# MotorController.net
KiCad netlist of a schematic drawn in EAGLE
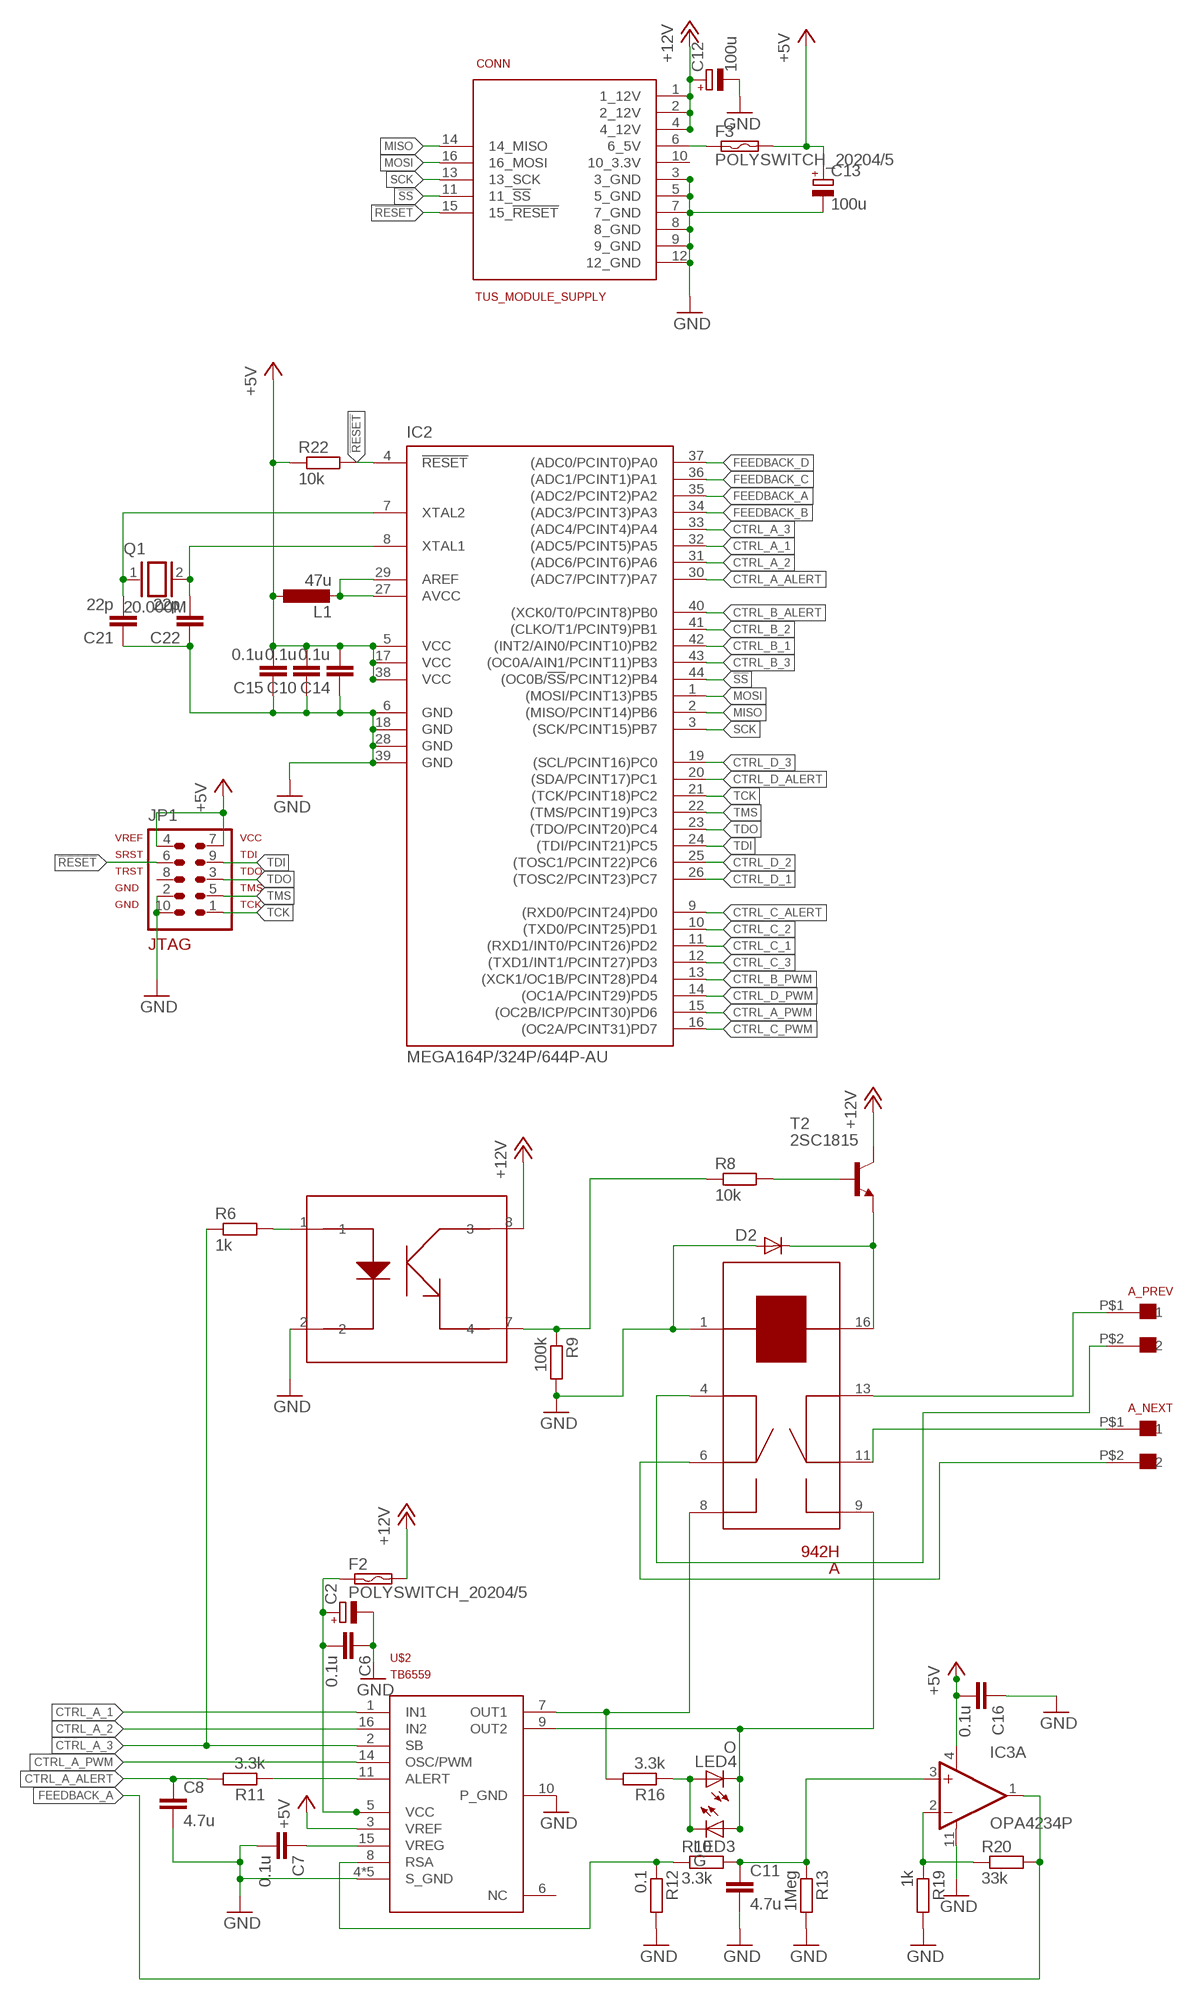
[diagram p0: schematic, sheet 1, part 1 of 2]
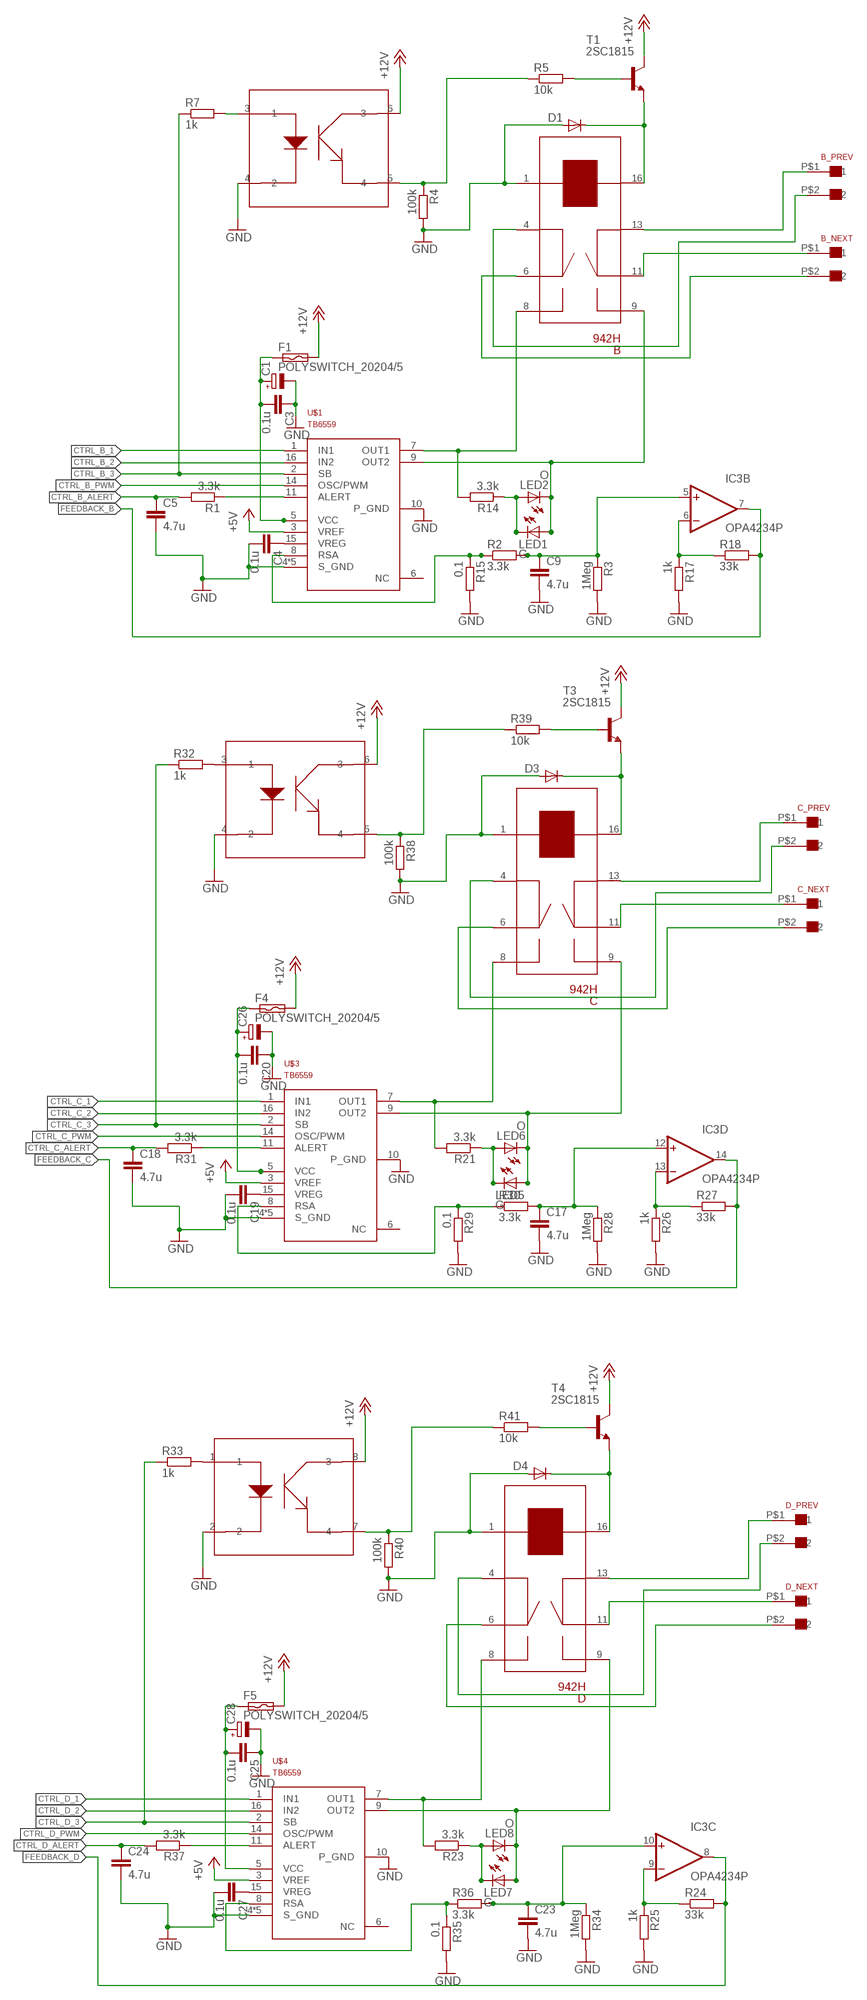
[diagram p1: schematic, sheet 1, part 2 of 2]

(export (version "E")
  (design (tool "Eeschema 10.0.6"))
  (components
    (comp (ref "A")
      (value "942H")
      (footprint "eagle-import:941H-2C-12D")
      (libsource (lib "eagle-import") (part "942H"))
    )
    (comp (ref "A_NEXT")
      (value "XH-2")
      (footprint "eagle-import:XH-2")
      (libsource (lib "eagle-import") (part "XH-2"))
    )
    (comp (ref "A_PREV")
      (value "XH-2")
      (footprint "eagle-import:XH-2")
      (libsource (lib "eagle-import") (part "XH-2"))
    )
    (comp (ref "B")
      (value "942H")
      (footprint "eagle-import:941H-2C-12D")
      (libsource (lib "eagle-import") (part "942H"))
    )
    (comp (ref "B_NEXT")
      (value "XH-2")
      (footprint "eagle-import:XH-2")
      (libsource (lib "eagle-import") (part "XH-2"))
    )
    (comp (ref "B_PREV")
      (value "XH-2")
      (footprint "eagle-import:XH-2")
      (libsource (lib "eagle-import") (part "XH-2"))
    )
    (comp (ref "C")
      (value "942H")
      (footprint "eagle-import:941H-2C-12D")
      (libsource (lib "eagle-import") (part "942H"))
    )
    (comp (ref "C1")
      (value "CPOL-EUE2,5-6E")
      (footprint "eagle-import:E2,5-6E")
      (libsource (lib "eagle-import") (part "CPOL-EUE2,5-6E"))
    )
    (comp (ref "C2")
      (value "CPOL-EUE2,5-6E")
      (footprint "eagle-import:E2,5-6E")
      (libsource (lib "eagle-import") (part "CPOL-EUE2,5-6E"))
    )
    (comp (ref "C3")
      (value "0.1u")
      (footprint "eagle-import:C0603")
      (libsource (lib "eagle-import") (part "C-EUC0603"))
    )
    (comp (ref "C4")
      (value "0.1u")
      (footprint "eagle-import:C0603")
      (libsource (lib "eagle-import") (part "C-EUC0603"))
    )
    (comp (ref "C5")
      (value "4.7u")
      (footprint "eagle-import:C0603")
      (libsource (lib "eagle-import") (part "C-EUC0603"))
    )
    (comp (ref "C6")
      (value "0.1u")
      (footprint "eagle-import:C0603")
      (libsource (lib "eagle-import") (part "C-EUC0603"))
    )
    (comp (ref "C7")
      (value "0.1u")
      (footprint "eagle-import:C0603")
      (libsource (lib "eagle-import") (part "C-EUC0603"))
    )
    (comp (ref "C8")
      (value "4.7u")
      (footprint "eagle-import:C0603")
      (libsource (lib "eagle-import") (part "C-EUC0603"))
    )
    (comp (ref "C9")
      (value "4.7u")
      (footprint "eagle-import:C0603")
      (libsource (lib "eagle-import") (part "C-EUC0603"))
    )
    (comp (ref "C10")
      (value "0.1u")
      (footprint "eagle-import:C0603")
      (libsource (lib "eagle-import") (part "C-EUC0603"))
    )
    (comp (ref "C11")
      (value "4.7u")
      (footprint "eagle-import:C0603")
      (libsource (lib "eagle-import") (part "C-EUC0603"))
    )
    (comp (ref "C12")
      (value "100u")
      (footprint "eagle-import:E2,5-6")
      (libsource (lib "eagle-import") (part "CPOL-EUE2.5-6"))
    )
    (comp (ref "C13")
      (value "100u")
      (footprint "eagle-import:E2-5")
      (libsource (lib "eagle-import") (part "CPOL-EUE2-5"))
    )
    (comp (ref "C14")
      (value "0.1u")
      (footprint "eagle-import:C0603")
      (libsource (lib "eagle-import") (part "C-EUC0603"))
    )
    (comp (ref "C15")
      (value "0.1u")
      (footprint "eagle-import:C0603")
      (libsource (lib "eagle-import") (part "C-EUC0603"))
    )
    (comp (ref "C16")
      (value "0.1u")
      (footprint "eagle-import:C0603")
      (libsource (lib "eagle-import") (part "C-EUC0603"))
    )
    (comp (ref "C17")
      (value "4.7u")
      (footprint "eagle-import:C0603")
      (libsource (lib "eagle-import") (part "C-EUC0603"))
    )
    (comp (ref "C18")
      (value "4.7u")
      (footprint "eagle-import:C0603")
      (libsource (lib "eagle-import") (part "C-EUC0603"))
    )
    (comp (ref "C19")
      (value "0.1u")
      (footprint "eagle-import:C0603")
      (libsource (lib "eagle-import") (part "C-EUC0603"))
    )
    (comp (ref "C20")
      (value "0.1u")
      (footprint "eagle-import:C0603")
      (libsource (lib "eagle-import") (part "C-EUC0603"))
    )
    (comp (ref "C21")
      (value "22p")
      (footprint "eagle-import:C0603")
      (libsource (lib "eagle-import") (part "C-EUC0603"))
    )
    (comp (ref "C22")
      (value "22p")
      (footprint "eagle-import:C0603")
      (libsource (lib "eagle-import") (part "C-EUC0603"))
    )
    (comp (ref "C23")
      (value "4.7u")
      (footprint "eagle-import:C0603")
      (libsource (lib "eagle-import") (part "C-EUC0603"))
    )
    (comp (ref "C24")
      (value "4.7u")
      (footprint "eagle-import:C0603")
      (libsource (lib "eagle-import") (part "C-EUC0603"))
    )
    (comp (ref "C25")
      (value "0.1u")
      (footprint "eagle-import:C0603")
      (libsource (lib "eagle-import") (part "C-EUC0603"))
    )
    (comp (ref "C26")
      (value "CPOL-EUE2,5-6E")
      (footprint "eagle-import:E2,5-6E")
      (libsource (lib "eagle-import") (part "CPOL-EUE2,5-6E"))
    )
    (comp (ref "C27")
      (value "0.1u")
      (footprint "eagle-import:C0603")
      (libsource (lib "eagle-import") (part "C-EUC0603"))
    )
    (comp (ref "C28")
      (value "CPOL-EUE2,5-6E")
      (footprint "eagle-import:E2,5-6E")
      (libsource (lib "eagle-import") (part "CPOL-EUE2,5-6E"))
    )
    (comp (ref "CONN")
      (value "TUS_MODULE_SUPPLY")
      (footprint "eagle-import:2X08")
      (libsource (lib "eagle-import") (part "TUS_MODULE_SUPPLY"))
    )
    (comp (ref "C_NEXT")
      (value "XH-2")
      (footprint "eagle-import:XH-2")
      (libsource (lib "eagle-import") (part "XH-2"))
    )
    (comp (ref "C_PREV")
      (value "XH-2")
      (footprint "eagle-import:XH-2")
      (libsource (lib "eagle-import") (part "XH-2"))
    )
    (comp (ref "D")
      (value "942H")
      (footprint "eagle-import:941H-2C-12D")
      (libsource (lib "eagle-import") (part "942H"))
    )
    (comp (ref "D1")
      (value "1N4148DO35-7")
      (footprint "eagle-import:DO35-7")
      (libsource (lib "eagle-import") (part "1N4148DO35-7"))
    )
    (comp (ref "D2")
      (value "1N4148DO35-7")
      (footprint "eagle-import:DO35-7")
      (libsource (lib "eagle-import") (part "1N4148DO35-7"))
    )
    (comp (ref "D3")
      (value "1N4148DO35-7")
      (footprint "eagle-import:DO35-7")
      (libsource (lib "eagle-import") (part "1N4148DO35-7"))
    )
    (comp (ref "D4")
      (value "1N4148DO35-7")
      (footprint "eagle-import:DO35-7")
      (libsource (lib "eagle-import") (part "1N4148DO35-7"))
    )
    (comp (ref "D_NEXT")
      (value "XH-2")
      (footprint "eagle-import:XH-2")
      (libsource (lib "eagle-import") (part "XH-2"))
    )
    (comp (ref "D_PREV")
      (value "XH-2")
      (footprint "eagle-import:XH-2")
      (libsource (lib "eagle-import") (part "XH-2"))
    )
    (comp (ref "F1")
      (value "POLYSWITCH_20204/5")
      (footprint "eagle-import:0204_5")
      (libsource (lib "eagle-import") (part "POLYSWITCH_20204/5"))
    )
    (comp (ref "F2")
      (value "POLYSWITCH_20204/5")
      (footprint "eagle-import:0204_5")
      (libsource (lib "eagle-import") (part "POLYSWITCH_20204/5"))
    )
    (comp (ref "F3")
      (value "POLYSWITCH_20204/5")
      (footprint "eagle-import:0204_5")
      (libsource (lib "eagle-import") (part "POLYSWITCH_20204/5"))
    )
    (comp (ref "F4")
      (value "POLYSWITCH_20204/5")
      (footprint "eagle-import:0204_5")
      (libsource (lib "eagle-import") (part "POLYSWITCH_20204/5"))
    )
    (comp (ref "F5")
      (value "POLYSWITCH_20204/5")
      (footprint "eagle-import:0204_5")
      (libsource (lib "eagle-import") (part "POLYSWITCH_20204/5"))
    )
    (comp (ref "IC1")
      (value "TLP621-2")
      (footprint "eagle-import:SOCKET-08")
      (libsource (lib "eagle-import") (part "TLP621-2"))
    )
    (comp (ref "IC2")
      (value "MEGA164P/324P/644P-AU")
      (footprint "eagle-import:TQFP44")
      (libsource (lib "eagle-import") (part "MEGA164P/324P/644P-AU"))
    )
    (comp (ref "IC3")
      (value "OPA4234P")
      (footprint "eagle-import:DIL14")
      (libsource (lib "eagle-import") (part "OPA4234P"))
    )
    (comp (ref "IC4")
      (value "TLP621-2")
      (footprint "eagle-import:SOCKET-08")
      (libsource (lib "eagle-import") (part "TLP621-2"))
    )
    (comp (ref "JP1")
      (value "AVR-JTAG-10")
      (footprint "eagle-import:AVR-JTAG-10")
      (libsource (lib "eagle-import") (part "AVR-JTAG-10"))
    )
    (comp (ref "L1")
      (value "47u")
      (footprint "eagle-import:L3216C")
      (libsource (lib "eagle-import") (part "L-EUL3216C"))
    )
    (comp (ref "LED1")
      (value "G")
      (footprint "eagle-import:LED3MM")
      (libsource (lib "eagle-import") (part "LED3MM"))
    )
    (comp (ref "LED2")
      (value "O")
      (footprint "eagle-import:LED3MM")
      (libsource (lib "eagle-import") (part "LED3MM"))
    )
    (comp (ref "LED3")
      (value "G")
      (footprint "eagle-import:LED3MM")
      (libsource (lib "eagle-import") (part "LED3MM"))
    )
    (comp (ref "LED4")
      (value "O")
      (footprint "eagle-import:LED3MM")
      (libsource (lib "eagle-import") (part "LED3MM"))
    )
    (comp (ref "LED5")
      (value "G")
      (footprint "eagle-import:LED3MM")
      (libsource (lib "eagle-import") (part "LED3MM"))
    )
    (comp (ref "LED6")
      (value "O")
      (footprint "eagle-import:LED3MM")
      (libsource (lib "eagle-import") (part "LED3MM"))
    )
    (comp (ref "LED7")
      (value "G")
      (footprint "eagle-import:LED3MM")
      (libsource (lib "eagle-import") (part "LED3MM"))
    )
    (comp (ref "LED8")
      (value "O")
      (footprint "eagle-import:LED3MM")
      (libsource (lib "eagle-import") (part "LED3MM"))
    )
    (comp (ref "Q1")
      (value "20.000M")
      (footprint "eagle-import:QS")
      (libsource (lib "eagle-import") (part "XTAL/S"))
    )
    (comp (ref "R1")
      (value "3.3k")
      (footprint "eagle-import:R0603")
      (libsource (lib "eagle-import") (part "R-EU_R0603"))
    )
    (comp (ref "R2")
      (value "3.3k")
      (footprint "eagle-import:R0603")
      (libsource (lib "eagle-import") (part "R-EU_R0603"))
    )
    (comp (ref "R3")
      (value "1Meg")
      (footprint "eagle-import:R0603")
      (libsource (lib "eagle-import") (part "R-EU_R0603"))
    )
    (comp (ref "R4")
      (value "100k")
      (footprint "eagle-import:R0603")
      (libsource (lib "eagle-import") (part "R-EU_R0603"))
    )
    (comp (ref "R5")
      (value "10k")
      (footprint "eagle-import:R0603")
      (libsource (lib "eagle-import") (part "R-EU_R0603"))
    )
    (comp (ref "R6")
      (value "1k")
      (footprint "eagle-import:R0603")
      (libsource (lib "eagle-import") (part "R-EU_R0603"))
    )
    (comp (ref "R7")
      (value "1k")
      (footprint "eagle-import:R0603")
      (libsource (lib "eagle-import") (part "R-EU_R0603"))
    )
    (comp (ref "R8")
      (value "10k")
      (footprint "eagle-import:R0603")
      (libsource (lib "eagle-import") (part "R-EU_R0603"))
    )
    (comp (ref "R9")
      (value "100k")
      (footprint "eagle-import:R0603")
      (libsource (lib "eagle-import") (part "R-EU_R0603"))
    )
    (comp (ref "R10")
      (value "3.3k")
      (footprint "eagle-import:R0603")
      (libsource (lib "eagle-import") (part "R-EU_R0603"))
    )
    (comp (ref "R11")
      (value "3.3k")
      (footprint "eagle-import:R0603")
      (libsource (lib "eagle-import") (part "R-EU_R0603"))
    )
    (comp (ref "R12")
      (value "0.1")
      (footprint "eagle-import:R1206")
      (libsource (lib "eagle-import") (part "R-EU_R1206"))
    )
    (comp (ref "R13")
      (value "1Meg")
      (footprint "eagle-import:R0603")
      (libsource (lib "eagle-import") (part "R-EU_R0603"))
    )
    (comp (ref "R14")
      (value "3.3k")
      (footprint "eagle-import:R0603")
      (libsource (lib "eagle-import") (part "R-EU_R0603"))
    )
    (comp (ref "R15")
      (value "0.1")
      (footprint "eagle-import:R1206")
      (libsource (lib "eagle-import") (part "R-EU_R1206"))
    )
    (comp (ref "R16")
      (value "3.3k")
      (footprint "eagle-import:R0603")
      (libsource (lib "eagle-import") (part "R-EU_R0603"))
    )
    (comp (ref "R17")
      (value "1k")
      (footprint "eagle-import:R0603")
      (libsource (lib "eagle-import") (part "R-EU_R0603"))
    )
    (comp (ref "R18")
      (value "33k")
      (footprint "eagle-import:R0603")
      (libsource (lib "eagle-import") (part "R-EU_R0603"))
    )
    (comp (ref "R19")
      (value "1k")
      (footprint "eagle-import:R0603")
      (libsource (lib "eagle-import") (part "R-EU_R0603"))
    )
    (comp (ref "R20")
      (value "33k")
      (footprint "eagle-import:R0603")
      (libsource (lib "eagle-import") (part "R-EU_R0603"))
    )
    (comp (ref "R21")
      (value "3.3k")
      (footprint "eagle-import:R0603")
      (libsource (lib "eagle-import") (part "R-EU_R0603"))
    )
    (comp (ref "R22")
      (value "10k")
      (footprint "eagle-import:R0603")
      (libsource (lib "eagle-import") (part "R-EU_R0603"))
    )
    (comp (ref "R23")
      (value "3.3k")
      (footprint "eagle-import:R0603")
      (libsource (lib "eagle-import") (part "R-EU_R0603"))
    )
    (comp (ref "R24")
      (value "33k")
      (footprint "eagle-import:R0603")
      (libsource (lib "eagle-import") (part "R-EU_R0603"))
    )
    (comp (ref "R25")
      (value "1k")
      (footprint "eagle-import:R0603")
      (libsource (lib "eagle-import") (part "R-EU_R0603"))
    )
    (comp (ref "R26")
      (value "1k")
      (footprint "eagle-import:R0603")
      (libsource (lib "eagle-import") (part "R-EU_R0603"))
    )
    (comp (ref "R27")
      (value "33k")
      (footprint "eagle-import:R0603")
      (libsource (lib "eagle-import") (part "R-EU_R0603"))
    )
    (comp (ref "R28")
      (value "1Meg")
      (footprint "eagle-import:R0603")
      (libsource (lib "eagle-import") (part "R-EU_R0603"))
    )
    (comp (ref "R29")
      (value "0.1")
      (footprint "eagle-import:R1206")
      (libsource (lib "eagle-import") (part "R-EU_R1206"))
    )
    (comp (ref "R30")
      (value "3.3k")
      (footprint "eagle-import:R0603")
      (libsource (lib "eagle-import") (part "R-EU_R0603"))
    )
    (comp (ref "R31")
      (value "3.3k")
      (footprint "eagle-import:R0603")
      (libsource (lib "eagle-import") (part "R-EU_R0603"))
    )
    (comp (ref "R32")
      (value "1k")
      (footprint "eagle-import:R0603")
      (libsource (lib "eagle-import") (part "R-EU_R0603"))
    )
    (comp (ref "R33")
      (value "1k")
      (footprint "eagle-import:R0603")
      (libsource (lib "eagle-import") (part "R-EU_R0603"))
    )
    (comp (ref "R34")
      (value "1Meg")
      (footprint "eagle-import:R0603")
      (libsource (lib "eagle-import") (part "R-EU_R0603"))
    )
    (comp (ref "R35")
      (value "0.1")
      (footprint "eagle-import:R1206")
      (libsource (lib "eagle-import") (part "R-EU_R1206"))
    )
    (comp (ref "R36")
      (value "3.3k")
      (footprint "eagle-import:R0603")
      (libsource (lib "eagle-import") (part "R-EU_R0603"))
    )
    (comp (ref "R37")
      (value "3.3k")
      (footprint "eagle-import:R0603")
      (libsource (lib "eagle-import") (part "R-EU_R0603"))
    )
    (comp (ref "R38")
      (value "100k")
      (footprint "eagle-import:R0603")
      (libsource (lib "eagle-import") (part "R-EU_R0603"))
    )
    (comp (ref "R39")
      (value "10k")
      (footprint "eagle-import:R0603")
      (libsource (lib "eagle-import") (part "R-EU_R0603"))
    )
    (comp (ref "R40")
      (value "100k")
      (footprint "eagle-import:R0603")
      (libsource (lib "eagle-import") (part "R-EU_R0603"))
    )
    (comp (ref "R41")
      (value "10k")
      (footprint "eagle-import:R0603")
      (libsource (lib "eagle-import") (part "R-EU_R0603"))
    )
    (comp (ref "T1")
      (value "2SC1815")
      (footprint "eagle-import:TO92-ECB")
      (libsource (lib "eagle-import") (part "2SC1815"))
    )
    (comp (ref "T2")
      (value "2SC1815")
      (footprint "eagle-import:TO92-ECB")
      (libsource (lib "eagle-import") (part "2SC1815"))
    )
    (comp (ref "T3")
      (value "2SC1815")
      (footprint "eagle-import:TO92-ECB")
      (libsource (lib "eagle-import") (part "2SC1815"))
    )
    (comp (ref "T4")
      (value "2SC1815")
      (footprint "eagle-import:TO92-ECB")
      (libsource (lib "eagle-import") (part "2SC1815"))
    )
    (comp (ref "U$1")
      (value "TB6559")
      (footprint "eagle-import:HSOP-16")
      (libsource (lib "eagle-import") (part "TB6559"))
    )
    (comp (ref "U$2")
      (value "TB6559")
      (footprint "eagle-import:HSOP-16")
      (libsource (lib "eagle-import") (part "TB6559"))
    )
    (comp (ref "U$3")
      (value "TB6559")
      (footprint "eagle-import:HSOP-16")
      (libsource (lib "eagle-import") (part "TB6559"))
    )
    (comp (ref "U$4")
      (value "TB6559")
      (footprint "eagle-import:HSOP-16")
      (libsource (lib "eagle-import") (part "TB6559"))
    )
  )
  (nets
    (net (code "1") (name "+5V") (class "Default")
      (node (ref "C10") (pin "2") (pinfunction "2_2") (pintype "passive"))
      (node (ref "C13") (pin "+") (pinfunction "+_+") (pintype "passive"))
      (node (ref "C14") (pin "2") (pinfunction "2_2") (pintype "passive"))
      (node (ref "C15") (pin "2") (pinfunction "2_2") (pintype "passive"))
      (node (ref "C16") (pin "2") (pinfunction "2_2") (pintype "passive"))
      (node (ref "F3") (pin "2") (pinfunction "2_2") (pintype "passive"))
      (node (ref "IC2") (pin "17") (pinfunction "VCC_17") (pintype "power_in"))
      (node (ref "IC2") (pin "38") (pinfunction "VCC_38") (pintype "power_in"))
      (node (ref "IC2") (pin "5") (pinfunction "VCC_5") (pintype "power_in"))
      (node (ref "IC3") (pin "4") (pinfunction "V+_4") (pintype "power_in"))
      (node (ref "JP1") (pin "4") (pinfunction "4_4") (pintype "passive"))
      (node (ref "JP1") (pin "7") (pinfunction "7_7") (pintype "passive"))
      (node (ref "L1") (pin "1") (pinfunction "1_1") (pintype "passive"))
      (node (ref "R22") (pin "1") (pinfunction "1_1") (pintype "passive"))
      (node (ref "U$1") (pin "3") (pinfunction "VREF_3") (pintype "bidirectional"))
      (node (ref "U$2") (pin "3") (pinfunction "VREF_3") (pintype "bidirectional"))
      (node (ref "U$3") (pin "3") (pinfunction "VREF_3") (pintype "bidirectional"))
      (node (ref "U$4") (pin "3") (pinfunction "VREF_3") (pintype "bidirectional"))
    )
    (net (code "2") (name "+12V") (class "Default")
      (node (ref "C12") (pin "+") (pinfunction "+_+") (pintype "passive"))
      (node (ref "CONN") (pin "1") (pinfunction "1_12V_1") (pintype "bidirectional"))
      (node (ref "CONN") (pin "2") (pinfunction "2_12V_2") (pintype "bidirectional"))
      (node (ref "CONN") (pin "4") (pinfunction "4_12V_4") (pintype "bidirectional"))
      (node (ref "F1") (pin "2") (pinfunction "2_2") (pintype "passive"))
      (node (ref "F2") (pin "2") (pinfunction "2_2") (pintype "passive"))
      (node (ref "F4") (pin "2") (pinfunction "2_2") (pintype "passive"))
      (node (ref "F5") (pin "2") (pinfunction "2_2") (pintype "passive"))
      (node (ref "IC1") (pin "6") (pinfunction "3_6") (pintype "bidirectional"))
      (node (ref "IC1") (pin "8") (pinfunction "3_8") (pintype "bidirectional"))
      (node (ref "IC4") (pin "6") (pinfunction "3_6") (pintype "bidirectional"))
      (node (ref "IC4") (pin "8") (pinfunction "3_8") (pintype "bidirectional"))
      (node (ref "T1") (pin "C") (pinfunction "C_C") (pintype "passive"))
      (node (ref "T2") (pin "C") (pinfunction "C_C") (pintype "passive"))
      (node (ref "T3") (pin "C") (pinfunction "C_C") (pintype "passive"))
      (node (ref "T4") (pin "C") (pinfunction "C_C") (pintype "passive"))
    )
    (net (code "3") (name "/~{RESET}") (class "Default")
      (node (ref "CONN") (pin "15") (pinfunction "15_~{RESET}_15") (pintype "bidirectional"))
      (node (ref "IC2") (pin "4") (pinfunction "~{RESET}_4") (pintype "input"))
      (node (ref "JP1") (pin "6") (pinfunction "6_6") (pintype "passive"))
      (node (ref "R22") (pin "2") (pinfunction "2_2") (pintype "passive"))
    )
    (net (code "4") (name "/~{SS}") (class "Default")
      (node (ref "CONN") (pin "11") (pinfunction "11_~{SS}_11") (pintype "bidirectional"))
      (node (ref "IC2") (pin "44") (pinfunction "(OC0B/~{SS}/PCINT12)PB4_44") (pintype "bidirectional"))
    )
    (net (code "5") (name "CTRL_A_1") (class "Default")
      (node (ref "IC2") (pin "32") (pinfunction "(ADC5/PCINT5)PA5_32") (pintype "bidirectional"))
      (node (ref "U$2") (pin "1") (pinfunction "IN1_1") (pintype "bidirectional"))
    )
    (net (code "6") (name "CTRL_A_2") (class "Default")
      (node (ref "IC2") (pin "31") (pinfunction "(ADC6/PCINT6)PA6_31") (pintype "bidirectional"))
      (node (ref "U$2") (pin "16") (pinfunction "IN2_16") (pintype "bidirectional"))
    )
    (net (code "7") (name "CTRL_A_3") (class "Default")
      (node (ref "IC2") (pin "33") (pinfunction "(ADC4/PCINT4)PA4_33") (pintype "bidirectional"))
      (node (ref "R6") (pin "1") (pinfunction "1_1") (pintype "passive"))
      (node (ref "U$2") (pin "2") (pinfunction "SB_2") (pintype "bidirectional"))
    )
    (net (code "8") (name "CTRL_A_ALERT") (class "Default")
      (node (ref "C8") (pin "1") (pinfunction "1_1") (pintype "passive"))
      (node (ref "IC2") (pin "30") (pinfunction "(ADC7/PCINT7)PA7_30") (pintype "bidirectional"))
      (node (ref "R11") (pin "2") (pinfunction "2_2") (pintype "passive"))
    )
    (net (code "9") (name "CTRL_A_PWM") (class "Default")
      (node (ref "IC2") (pin "15") (pinfunction "(OC2B/ICP/PCINT30)PD6_15") (pintype "bidirectional"))
      (node (ref "U$2") (pin "14") (pinfunction "OSC/PWM_14") (pintype "bidirectional"))
    )
    (net (code "10") (name "CTRL_B_1") (class "Default")
      (node (ref "IC2") (pin "42") (pinfunction "(INT2/AIN0/PCINT10)PB2_42") (pintype "bidirectional"))
      (node (ref "U$1") (pin "1") (pinfunction "IN1_1") (pintype "bidirectional"))
    )
    (net (code "11") (name "CTRL_B_2") (class "Default")
      (node (ref "IC2") (pin "41") (pinfunction "(CLKO/T1/PCINT9)PB1_41") (pintype "bidirectional"))
      (node (ref "U$1") (pin "16") (pinfunction "IN2_16") (pintype "bidirectional"))
    )
    (net (code "12") (name "CTRL_B_3") (class "Default")
      (node (ref "IC2") (pin "43") (pinfunction "(OC0A/AIN1/PCINT11)PB3_43") (pintype "bidirectional"))
      (node (ref "R7") (pin "1") (pinfunction "1_1") (pintype "passive"))
      (node (ref "U$1") (pin "2") (pinfunction "SB_2") (pintype "bidirectional"))
    )
    (net (code "13") (name "CTRL_B_ALERT") (class "Default")
      (node (ref "C5") (pin "1") (pinfunction "1_1") (pintype "passive"))
      (node (ref "IC2") (pin "40") (pinfunction "(XCK0/T0/PCINT8)PB0_40") (pintype "bidirectional"))
      (node (ref "R1") (pin "2") (pinfunction "2_2") (pintype "passive"))
    )
    (net (code "14") (name "CTRL_B_PWM") (class "Default")
      (node (ref "IC2") (pin "13") (pinfunction "(XCK1/OC1B/PCINT28)PD4_13") (pintype "bidirectional"))
      (node (ref "U$1") (pin "14") (pinfunction "OSC/PWM_14") (pintype "bidirectional"))
    )
    (net (code "15") (name "CTRL_C_1") (class "Default")
      (node (ref "IC2") (pin "11") (pinfunction "(RXD1/INT0/PCINT26)PD2_11") (pintype "bidirectional"))
      (node (ref "U$3") (pin "1") (pinfunction "IN1_1") (pintype "bidirectional"))
    )
    (net (code "16") (name "CTRL_C_2") (class "Default")
      (node (ref "IC2") (pin "10") (pinfunction "(TXD0/PCINT25)PD1_10") (pintype "bidirectional"))
      (node (ref "U$3") (pin "16") (pinfunction "IN2_16") (pintype "bidirectional"))
    )
    (net (code "17") (name "CTRL_C_3") (class "Default")
      (node (ref "IC2") (pin "12") (pinfunction "(TXD1/INT1/PCINT27)PD3_12") (pintype "bidirectional"))
      (node (ref "R32") (pin "1") (pinfunction "1_1") (pintype "passive"))
      (node (ref "U$3") (pin "2") (pinfunction "SB_2") (pintype "bidirectional"))
    )
    (net (code "18") (name "CTRL_C_ALERT") (class "Default")
      (node (ref "C18") (pin "1") (pinfunction "1_1") (pintype "passive"))
      (node (ref "IC2") (pin "9") (pinfunction "(RXD0/PCINT24)PD0_9") (pintype "bidirectional"))
      (node (ref "R31") (pin "2") (pinfunction "2_2") (pintype "passive"))
    )
    (net (code "19") (name "CTRL_C_PWM") (class "Default")
      (node (ref "IC2") (pin "16") (pinfunction "(OC2A/PCINT31)PD7_16") (pintype "bidirectional"))
      (node (ref "U$3") (pin "14") (pinfunction "OSC/PWM_14") (pintype "bidirectional"))
    )
    (net (code "20") (name "CTRL_D_1") (class "Default")
      (node (ref "IC2") (pin "26") (pinfunction "(TOSC2/PCINT23)PC7_26") (pintype "bidirectional"))
      (node (ref "U$4") (pin "1") (pinfunction "IN1_1") (pintype "bidirectional"))
    )
    (net (code "21") (name "CTRL_D_2") (class "Default")
      (node (ref "IC2") (pin "25") (pinfunction "(TOSC1/PCINT22)PC6_25") (pintype "bidirectional"))
      (node (ref "U$4") (pin "16") (pinfunction "IN2_16") (pintype "bidirectional"))
    )
    (net (code "22") (name "CTRL_D_3") (class "Default")
      (node (ref "IC2") (pin "19") (pinfunction "(SCL/PCINT16)PC0_19") (pintype "bidirectional"))
      (node (ref "R33") (pin "1") (pinfunction "1_1") (pintype "passive"))
      (node (ref "U$4") (pin "2") (pinfunction "SB_2") (pintype "bidirectional"))
    )
    (net (code "23") (name "CTRL_D_ALERT") (class "Default")
      (node (ref "C24") (pin "1") (pinfunction "1_1") (pintype "passive"))
      (node (ref "IC2") (pin "20") (pinfunction "(SDA/PCINT17)PC1_20") (pintype "bidirectional"))
      (node (ref "R37") (pin "2") (pinfunction "2_2") (pintype "passive"))
    )
    (net (code "24") (name "CTRL_D_PWM") (class "Default")
      (node (ref "IC2") (pin "14") (pinfunction "(OC1A/PCINT29)PD5_14") (pintype "bidirectional"))
      (node (ref "U$4") (pin "14") (pinfunction "OSC/PWM_14") (pintype "bidirectional"))
    )
    (net (code "25") (name "FEEDBACK_A") (class "Default")
      (node (ref "IC2") (pin "35") (pinfunction "(ADC2/PCINT2)PA2_35") (pintype "bidirectional"))
      (node (ref "IC3") (pin "1") (pinfunction "OUT_1") (pintype "output"))
      (node (ref "R20") (pin "2") (pinfunction "2_2") (pintype "passive"))
    )
    (net (code "26") (name "FEEDBACK_B") (class "Default")
      (node (ref "IC2") (pin "34") (pinfunction "(ADC3/PCINT3)PA3_34") (pintype "bidirectional"))
      (node (ref "IC3") (pin "7") (pinfunction "OUT_7") (pintype "output"))
      (node (ref "R18") (pin "2") (pinfunction "2_2") (pintype "passive"))
    )
    (net (code "27") (name "FEEDBACK_C") (class "Default")
      (node (ref "IC2") (pin "36") (pinfunction "(ADC1/PCINT1)PA1_36") (pintype "bidirectional"))
      (node (ref "IC3") (pin "14") (pinfunction "OUT_14") (pintype "output"))
      (node (ref "R27") (pin "2") (pinfunction "2_2") (pintype "passive"))
    )
    (net (code "28") (name "FEEDBACK_D") (class "Default")
      (node (ref "IC2") (pin "37") (pinfunction "(ADC0/PCINT0)PA0_37") (pintype "bidirectional"))
      (node (ref "IC3") (pin "8") (pinfunction "OUT_8") (pintype "output"))
      (node (ref "R24") (pin "2") (pinfunction "2_2") (pintype "passive"))
    )
    (net (code "29") (name "GND") (class "Default")
      (node (ref "A") (pin "1") (pinfunction "4_1") (pintype "bidirectional"))
      (node (ref "B") (pin "1") (pinfunction "4_1") (pintype "bidirectional"))
      (node (ref "C") (pin "1") (pinfunction "4_1") (pintype "bidirectional"))
      (node (ref "C1") (pin "-") (pinfunction "-_-") (pintype "passive"))
      (node (ref "C10") (pin "1") (pinfunction "1_1") (pintype "passive"))
      (node (ref "C11") (pin "2") (pinfunction "2_2") (pintype "passive"))
      (node (ref "C12") (pin "-") (pinfunction "-_-") (pintype "passive"))
      (node (ref "C13") (pin "-") (pinfunction "-_-") (pintype "passive"))
      (node (ref "C14") (pin "1") (pinfunction "1_1") (pintype "passive"))
      (node (ref "C15") (pin "1") (pinfunction "1_1") (pintype "passive"))
      (node (ref "C16") (pin "1") (pinfunction "1_1") (pintype "passive"))
      (node (ref "C17") (pin "2") (pinfunction "2_2") (pintype "passive"))
      (node (ref "C18") (pin "2") (pinfunction "2_2") (pintype "passive"))
      (node (ref "C19") (pin "2") (pinfunction "2_2") (pintype "passive"))
      (node (ref "C2") (pin "-") (pinfunction "-_-") (pintype "passive"))
      (node (ref "C20") (pin "1") (pinfunction "1_1") (pintype "passive"))
      (node (ref "C21") (pin "1") (pinfunction "1_1") (pintype "passive"))
      (node (ref "C22") (pin "1") (pinfunction "1_1") (pintype "passive"))
      (node (ref "C23") (pin "2") (pinfunction "2_2") (pintype "passive"))
      (node (ref "C24") (pin "2") (pinfunction "2_2") (pintype "passive"))
      (node (ref "C25") (pin "1") (pinfunction "1_1") (pintype "passive"))
      (node (ref "C26") (pin "-") (pinfunction "-_-") (pintype "passive"))
      (node (ref "C27") (pin "2") (pinfunction "2_2") (pintype "passive"))
      (node (ref "C28") (pin "-") (pinfunction "-_-") (pintype "passive"))
      (node (ref "C3") (pin "1") (pinfunction "1_1") (pintype "passive"))
      (node (ref "C4") (pin "2") (pinfunction "2_2") (pintype "passive"))
      (node (ref "C5") (pin "2") (pinfunction "2_2") (pintype "passive"))
      (node (ref "C6") (pin "1") (pinfunction "1_1") (pintype "passive"))
      (node (ref "C7") (pin "2") (pinfunction "2_2") (pintype "passive"))
      (node (ref "C8") (pin "2") (pinfunction "2_2") (pintype "passive"))
      (node (ref "C9") (pin "2") (pinfunction "2_2") (pintype "passive"))
      (node (ref "CONN") (pin "12") (pinfunction "12_GND_12") (pintype "bidirectional"))
      (node (ref "CONN") (pin "3") (pinfunction "3_GND_3") (pintype "bidirectional"))
      (node (ref "CONN") (pin "5") (pinfunction "5_GND_5") (pintype "bidirectional"))
      (node (ref "CONN") (pin "7") (pinfunction "7_GND_7") (pintype "bidirectional"))
      (node (ref "CONN") (pin "8") (pinfunction "8_GND_8") (pintype "bidirectional"))
      (node (ref "CONN") (pin "9") (pinfunction "9_GND_9") (pintype "bidirectional"))
      (node (ref "D") (pin "1") (pinfunction "4_1") (pintype "bidirectional"))
      (node (ref "D1") (pin "A") (pinfunction "A_A") (pintype "passive"))
      (node (ref "D2") (pin "A") (pinfunction "A_A") (pintype "passive"))
      (node (ref "D3") (pin "A") (pinfunction "A_A") (pintype "passive"))
      (node (ref "D4") (pin "A") (pinfunction "A_A") (pintype "passive"))
      (node (ref "IC1") (pin "2") (pinfunction "2_2") (pintype "bidirectional"))
      (node (ref "IC1") (pin "4") (pinfunction "2_4") (pintype "bidirectional"))
      (node (ref "IC2") (pin "18") (pinfunction "GND_18") (pintype "power_in"))
      (node (ref "IC2") (pin "28") (pinfunction "GND_28") (pintype "power_in"))
      (node (ref "IC2") (pin "39") (pinfunction "GND_39") (pintype "power_in"))
      (node (ref "IC2") (pin "6") (pinfunction "GND_6") (pintype "power_in"))
      (node (ref "IC3") (pin "11") (pinfunction "V-_11") (pintype "power_in"))
      (node (ref "IC4") (pin "2") (pinfunction "2_2") (pintype "bidirectional"))
      (node (ref "IC4") (pin "4") (pinfunction "2_4") (pintype "bidirectional"))
      (node (ref "JP1") (pin "10") (pinfunction "10_10") (pintype "passive"))
      (node (ref "JP1") (pin "2") (pinfunction "2_2") (pintype "passive"))
      (node (ref "R12") (pin "2") (pinfunction "2_2") (pintype "passive"))
      (node (ref "R13") (pin "2") (pinfunction "2_2") (pintype "passive"))
      (node (ref "R15") (pin "2") (pinfunction "2_2") (pintype "passive"))
      (node (ref "R17") (pin "2") (pinfunction "2_2") (pintype "passive"))
      (node (ref "R19") (pin "2") (pinfunction "2_2") (pintype "passive"))
      (node (ref "R25") (pin "2") (pinfunction "2_2") (pintype "passive"))
      (node (ref "R26") (pin "2") (pinfunction "2_2") (pintype "passive"))
      (node (ref "R28") (pin "2") (pinfunction "2_2") (pintype "passive"))
      (node (ref "R29") (pin "2") (pinfunction "2_2") (pintype "passive"))
      (node (ref "R3") (pin "2") (pinfunction "2_2") (pintype "passive"))
      (node (ref "R34") (pin "2") (pinfunction "2_2") (pintype "passive"))
      (node (ref "R35") (pin "2") (pinfunction "2_2") (pintype "passive"))
      (node (ref "R38") (pin "2") (pinfunction "2_2") (pintype "passive"))
      (node (ref "R4") (pin "2") (pinfunction "2_2") (pintype "passive"))
      (node (ref "R40") (pin "2") (pinfunction "2_2") (pintype "passive"))
      (node (ref "R9") (pin "2") (pinfunction "2_2") (pintype "passive"))
      (node (ref "U$1") (pin "10") (pinfunction "P_GND_10") (pintype "bidirectional"))
      (node (ref "U$1") (pin "12") (pinfunction "S_GND_12") (pintype "bidirectional"))
      (node (ref "U$1") (pin "13") (pinfunction "S_GND_13") (pintype "bidirectional"))
      (node (ref "U$1") (pin "4") (pinfunction "S_GND_4") (pintype "bidirectional"))
      (node (ref "U$1") (pin "FIN_1") (pinfunction "S_GND_FIN_1") (pintype "bidirectional"))
      (node (ref "U$1") (pin "FIN_2") (pinfunction "S_GND_FIN_2") (pintype "bidirectional"))
      (node (ref "U$2") (pin "10") (pinfunction "P_GND_10") (pintype "bidirectional"))
      (node (ref "U$2") (pin "12") (pinfunction "S_GND_12") (pintype "bidirectional"))
      (node (ref "U$2") (pin "13") (pinfunction "S_GND_13") (pintype "bidirectional"))
      (node (ref "U$2") (pin "4") (pinfunction "S_GND_4") (pintype "bidirectional"))
      (node (ref "U$2") (pin "FIN_1") (pinfunction "S_GND_FIN_1") (pintype "bidirectional"))
      (node (ref "U$2") (pin "FIN_2") (pinfunction "S_GND_FIN_2") (pintype "bidirectional"))
      (node (ref "U$3") (pin "10") (pinfunction "P_GND_10") (pintype "bidirectional"))
      (node (ref "U$3") (pin "12") (pinfunction "S_GND_12") (pintype "bidirectional"))
      (node (ref "U$3") (pin "13") (pinfunction "S_GND_13") (pintype "bidirectional"))
      (node (ref "U$3") (pin "4") (pinfunction "S_GND_4") (pintype "bidirectional"))
      (node (ref "U$3") (pin "FIN_1") (pinfunction "S_GND_FIN_1") (pintype "bidirectional"))
      (node (ref "U$3") (pin "FIN_2") (pinfunction "S_GND_FIN_2") (pintype "bidirectional"))
      (node (ref "U$4") (pin "10") (pinfunction "P_GND_10") (pintype "bidirectional"))
      (node (ref "U$4") (pin "12") (pinfunction "S_GND_12") (pintype "bidirectional"))
      (node (ref "U$4") (pin "13") (pinfunction "S_GND_13") (pintype "bidirectional"))
      (node (ref "U$4") (pin "4") (pinfunction "S_GND_4") (pintype "bidirectional"))
      (node (ref "U$4") (pin "FIN_1") (pinfunction "S_GND_FIN_1") (pintype "bidirectional"))
      (node (ref "U$4") (pin "FIN_2") (pinfunction "S_GND_FIN_2") (pintype "bidirectional"))
    )
    (net (code "30") (name "MISO") (class "Default")
      (node (ref "CONN") (pin "14") (pinfunction "14_MISO_14") (pintype "bidirectional"))
      (node (ref "IC2") (pin "2") (pinfunction "(MISO/PCINT14)PB6_2") (pintype "bidirectional"))
    )
    (net (code "31") (name "MOSI") (class "Default")
      (node (ref "CONN") (pin "16") (pinfunction "16_MOSI_16") (pintype "bidirectional"))
      (node (ref "IC2") (pin "1") (pinfunction "(MOSI/PCINT13)PB5_1") (pintype "bidirectional"))
    )
    (net (code "32") (name "Net-(A-'1)") (class "Default")
      (node (ref "A") (pin "9") (pinfunction "'1_9") (pintype "bidirectional"))
      (node (ref "LED3") (pin "A") (pinfunction "A_A") (pintype "passive"))
      (node (ref "LED4") (pin "K") (pinfunction "C_K") (pintype "passive"))
      (node (ref "U$2") (pin "9") (pinfunction "OUT2_9") (pintype "bidirectional"))
    )
    (net (code "33") (name "Net-(A-'2)") (class "Default")
      (node (ref "A") (pin "11") (pinfunction "'2_11") (pintype "bidirectional"))
      (node (ref "A_NEXT") (pin "P$1") (pinfunction "1_P$1") (pintype "bidirectional"))
    )
    (net (code "34") (name "Net-(A-'3)") (class "Default")
      (node (ref "A") (pin "13") (pinfunction "'3_13") (pintype "bidirectional"))
      (node (ref "A_PREV") (pin "P$1") (pinfunction "1_P$1") (pintype "bidirectional"))
    )
    (net (code "35") (name "Net-(A-'4)") (class "Default")
      (node (ref "A") (pin "16") (pinfunction "'4_16") (pintype "bidirectional"))
      (node (ref "D2") (pin "C") (pinfunction "C_C") (pintype "passive"))
      (node (ref "T2") (pin "E") (pinfunction "E_E") (pintype "passive"))
    )
    (net (code "36") (name "Net-(A-1)") (class "Default")
      (node (ref "A") (pin "8") (pinfunction "1_8") (pintype "bidirectional"))
      (node (ref "R16") (pin "2") (pinfunction "2_2") (pintype "passive"))
      (node (ref "U$2") (pin "7") (pinfunction "OUT1_7") (pintype "bidirectional"))
    )
    (net (code "37") (name "Net-(A-2)") (class "Default")
      (node (ref "A") (pin "6") (pinfunction "2_6") (pintype "bidirectional"))
      (node (ref "A_NEXT") (pin "P$2") (pinfunction "2_P$2") (pintype "bidirectional"))
    )
    (net (code "38") (name "Net-(A-3)") (class "Default")
      (node (ref "A") (pin "4") (pinfunction "3_4") (pintype "bidirectional"))
      (node (ref "A_PREV") (pin "P$2") (pinfunction "2_P$2") (pintype "bidirectional"))
    )
    (net (code "39") (name "Net-(B-'1)") (class "Default")
      (node (ref "B") (pin "9") (pinfunction "'1_9") (pintype "bidirectional"))
      (node (ref "LED1") (pin "A") (pinfunction "A_A") (pintype "passive"))
      (node (ref "LED2") (pin "K") (pinfunction "C_K") (pintype "passive"))
      (node (ref "U$1") (pin "9") (pinfunction "OUT2_9") (pintype "bidirectional"))
    )
    (net (code "40") (name "Net-(B-'2)") (class "Default")
      (node (ref "B") (pin "11") (pinfunction "'2_11") (pintype "bidirectional"))
      (node (ref "B_NEXT") (pin "P$1") (pinfunction "1_P$1") (pintype "bidirectional"))
    )
    (net (code "41") (name "Net-(B-'3)") (class "Default")
      (node (ref "B") (pin "13") (pinfunction "'3_13") (pintype "bidirectional"))
      (node (ref "B_PREV") (pin "P$1") (pinfunction "1_P$1") (pintype "bidirectional"))
    )
    (net (code "42") (name "Net-(B-'4)") (class "Default")
      (node (ref "B") (pin "16") (pinfunction "'4_16") (pintype "bidirectional"))
      (node (ref "D1") (pin "C") (pinfunction "C_C") (pintype "passive"))
      (node (ref "T1") (pin "E") (pinfunction "E_E") (pintype "passive"))
    )
    (net (code "43") (name "Net-(B-1)") (class "Default")
      (node (ref "B") (pin "8") (pinfunction "1_8") (pintype "bidirectional"))
      (node (ref "R14") (pin "2") (pinfunction "2_2") (pintype "passive"))
      (node (ref "U$1") (pin "7") (pinfunction "OUT1_7") (pintype "bidirectional"))
    )
    (net (code "44") (name "Net-(B-2)") (class "Default")
      (node (ref "B") (pin "6") (pinfunction "2_6") (pintype "bidirectional"))
      (node (ref "B_NEXT") (pin "P$2") (pinfunction "2_P$2") (pintype "bidirectional"))
    )
    (net (code "45") (name "Net-(B-3)") (class "Default")
      (node (ref "B") (pin "4") (pinfunction "3_4") (pintype "bidirectional"))
      (node (ref "B_PREV") (pin "P$2") (pinfunction "2_P$2") (pintype "bidirectional"))
    )
    (net (code "46") (name "Net-(C-'1)") (class "Default")
      (node (ref "C") (pin "9") (pinfunction "'1_9") (pintype "bidirectional"))
      (node (ref "LED5") (pin "A") (pinfunction "A_A") (pintype "passive"))
      (node (ref "LED6") (pin "K") (pinfunction "C_K") (pintype "passive"))
      (node (ref "U$3") (pin "9") (pinfunction "OUT2_9") (pintype "bidirectional"))
    )
    (net (code "47") (name "Net-(C-'2)") (class "Default")
      (node (ref "C") (pin "11") (pinfunction "'2_11") (pintype "bidirectional"))
      (node (ref "C_NEXT") (pin "P$1") (pinfunction "1_P$1") (pintype "bidirectional"))
    )
    (net (code "48") (name "Net-(C-'3)") (class "Default")
      (node (ref "C") (pin "13") (pinfunction "'3_13") (pintype "bidirectional"))
      (node (ref "C_PREV") (pin "P$1") (pinfunction "1_P$1") (pintype "bidirectional"))
    )
    (net (code "49") (name "Net-(C-'4)") (class "Default")
      (node (ref "C") (pin "16") (pinfunction "'4_16") (pintype "bidirectional"))
      (node (ref "D3") (pin "C") (pinfunction "C_C") (pintype "passive"))
      (node (ref "T3") (pin "E") (pinfunction "E_E") (pintype "passive"))
    )
    (net (code "50") (name "Net-(C-1)") (class "Default")
      (node (ref "C") (pin "8") (pinfunction "1_8") (pintype "bidirectional"))
      (node (ref "R21") (pin "2") (pinfunction "2_2") (pintype "passive"))
      (node (ref "U$3") (pin "7") (pinfunction "OUT1_7") (pintype "bidirectional"))
    )
    (net (code "51") (name "Net-(C-2)") (class "Default")
      (node (ref "C") (pin "6") (pinfunction "2_6") (pintype "bidirectional"))
      (node (ref "C_NEXT") (pin "P$2") (pinfunction "2_P$2") (pintype "bidirectional"))
    )
    (net (code "52") (name "Net-(C-3)") (class "Default")
      (node (ref "C") (pin "4") (pinfunction "3_4") (pintype "bidirectional"))
      (node (ref "C_PREV") (pin "P$2") (pinfunction "2_P$2") (pintype "bidirectional"))
    )
    (net (code "53") (name "Net-(CONN-6_5V)") (class "Default")
      (node (ref "CONN") (pin "6") (pinfunction "6_5V_6") (pintype "bidirectional"))
      (node (ref "F3") (pin "1") (pinfunction "1_1") (pintype "passive"))
    )
    (net (code "54") (name "Net-(D-'1)") (class "Default")
      (node (ref "D") (pin "9") (pinfunction "'1_9") (pintype "bidirectional"))
      (node (ref "LED7") (pin "A") (pinfunction "A_A") (pintype "passive"))
      (node (ref "LED8") (pin "K") (pinfunction "C_K") (pintype "passive"))
      (node (ref "U$4") (pin "9") (pinfunction "OUT2_9") (pintype "bidirectional"))
    )
    (net (code "55") (name "Net-(D-'2)") (class "Default")
      (node (ref "D") (pin "11") (pinfunction "'2_11") (pintype "bidirectional"))
      (node (ref "D_NEXT") (pin "P$1") (pinfunction "1_P$1") (pintype "bidirectional"))
    )
    (net (code "56") (name "Net-(D-'3)") (class "Default")
      (node (ref "D") (pin "13") (pinfunction "'3_13") (pintype "bidirectional"))
      (node (ref "D_PREV") (pin "P$1") (pinfunction "1_P$1") (pintype "bidirectional"))
    )
    (net (code "57") (name "Net-(D-'4)") (class "Default")
      (node (ref "D") (pin "16") (pinfunction "'4_16") (pintype "bidirectional"))
      (node (ref "D4") (pin "C") (pinfunction "C_C") (pintype "passive"))
      (node (ref "T4") (pin "E") (pinfunction "E_E") (pintype "passive"))
    )
    (net (code "58") (name "Net-(D-1)") (class "Default")
      (node (ref "D") (pin "8") (pinfunction "1_8") (pintype "bidirectional"))
      (node (ref "R23") (pin "2") (pinfunction "2_2") (pintype "passive"))
      (node (ref "U$4") (pin "7") (pinfunction "OUT1_7") (pintype "bidirectional"))
    )
    (net (code "59") (name "Net-(D-2)") (class "Default")
      (node (ref "D") (pin "6") (pinfunction "2_6") (pintype "bidirectional"))
      (node (ref "D_NEXT") (pin "P$2") (pinfunction "2_P$2") (pintype "bidirectional"))
    )
    (net (code "60") (name "Net-(D-3)") (class "Default")
      (node (ref "D") (pin "4") (pinfunction "3_4") (pintype "bidirectional"))
      (node (ref "D_PREV") (pin "P$2") (pinfunction "2_P$2") (pintype "bidirectional"))
    )
    (net (code "61") (name "Net-(IC1-Pad1)") (class "Default")
      (node (ref "IC1") (pin "1") (pinfunction "1_1") (pintype "bidirectional"))
      (node (ref "R6") (pin "2") (pinfunction "2_2") (pintype "passive"))
    )
    (net (code "62") (name "Net-(IC1A-4)") (class "Default")
      (node (ref "IC1") (pin "7") (pinfunction "4_7") (pintype "bidirectional"))
      (node (ref "R8") (pin "1") (pinfunction "1_1") (pintype "passive"))
      (node (ref "R9") (pin "1") (pinfunction "1_1") (pintype "passive"))
    )
    (net (code "63") (name "Net-(IC1B-1)") (class "Default")
      (node (ref "IC1") (pin "3") (pinfunction "1_3") (pintype "bidirectional"))
      (node (ref "R7") (pin "2") (pinfunction "2_2") (pintype "passive"))
    )
    (net (code "64") (name "Net-(IC1B-4)") (class "Default")
      (node (ref "IC1") (pin "5") (pinfunction "4_5") (pintype "bidirectional"))
      (node (ref "R4") (pin "1") (pinfunction "1_1") (pintype "passive"))
      (node (ref "R5") (pin "1") (pinfunction "1_1") (pintype "passive"))
    )
    (net (code "65") (name "Net-(IC2-AREF)") (class "Default")
      (node (ref "IC2") (pin "27") (pinfunction "AVCC_27") (pintype "power_in"))
      (node (ref "IC2") (pin "29") (pinfunction "AREF_29") (pintype "power_in"))
      (node (ref "L1") (pin "2") (pinfunction "2_2") (pintype "passive"))
    )
    (net (code "66") (name "Net-(IC2-XTAL1)") (class "Default")
      (node (ref "C22") (pin "2") (pinfunction "2_2") (pintype "passive"))
      (node (ref "IC2") (pin "8") (pinfunction "XTAL1_8") (pintype "input"))
      (node (ref "Q1") (pin "2") (pinfunction "2_2") (pintype "passive"))
    )
    (net (code "67") (name "Net-(IC2-XTAL2)") (class "Default")
      (node (ref "C21") (pin "2") (pinfunction "2_2") (pintype "passive"))
      (node (ref "IC2") (pin "7") (pinfunction "XTAL2_7") (pintype "output"))
      (node (ref "Q1") (pin "1") (pinfunction "1_1") (pintype "passive"))
    )
    (net (code "68") (name "Net-(IC3A-+IN)") (class "Default")
      (node (ref "C11") (pin "1") (pinfunction "1_1") (pintype "passive"))
      (node (ref "IC3") (pin "3") (pinfunction "+IN_3") (pintype "input"))
      (node (ref "R10") (pin "2") (pinfunction "2_2") (pintype "passive"))
      (node (ref "R13") (pin "1") (pinfunction "1_1") (pintype "passive"))
    )
    (net (code "69") (name "Net-(IC3A--IN)") (class "Default")
      (node (ref "IC3") (pin "2") (pinfunction "-IN_2") (pintype "input"))
      (node (ref "R19") (pin "1") (pinfunction "1_1") (pintype "passive"))
      (node (ref "R20") (pin "1") (pinfunction "1_1") (pintype "passive"))
    )
    (net (code "70") (name "Net-(IC3B-+IN)") (class "Default")
      (node (ref "C9") (pin "1") (pinfunction "1_1") (pintype "passive"))
      (node (ref "IC3") (pin "5") (pinfunction "+IN_5") (pintype "input"))
      (node (ref "R2") (pin "2") (pinfunction "2_2") (pintype "passive"))
      (node (ref "R3") (pin "1") (pinfunction "1_1") (pintype "passive"))
    )
    (net (code "71") (name "Net-(IC3B--IN)") (class "Default")
      (node (ref "IC3") (pin "6") (pinfunction "-IN_6") (pintype "input"))
      (node (ref "R17") (pin "1") (pinfunction "1_1") (pintype "passive"))
      (node (ref "R18") (pin "1") (pinfunction "1_1") (pintype "passive"))
    )
    (net (code "72") (name "Net-(IC3C-+IN)") (class "Default")
      (node (ref "C23") (pin "1") (pinfunction "1_1") (pintype "passive"))
      (node (ref "IC3") (pin "10") (pinfunction "+IN_10") (pintype "input"))
      (node (ref "R34") (pin "1") (pinfunction "1_1") (pintype "passive"))
      (node (ref "R36") (pin "2") (pinfunction "2_2") (pintype "passive"))
    )
    (net (code "73") (name "Net-(IC3C--IN)") (class "Default")
      (node (ref "IC3") (pin "9") (pinfunction "-IN_9") (pintype "input"))
      (node (ref "R24") (pin "1") (pinfunction "1_1") (pintype "passive"))
      (node (ref "R25") (pin "1") (pinfunction "1_1") (pintype "passive"))
    )
    (net (code "74") (name "Net-(IC3D-+IN)") (class "Default")
      (node (ref "C17") (pin "1") (pinfunction "1_1") (pintype "passive"))
      (node (ref "IC3") (pin "12") (pinfunction "+IN_12") (pintype "input"))
      (node (ref "R28") (pin "1") (pinfunction "1_1") (pintype "passive"))
      (node (ref "R30") (pin "2") (pinfunction "2_2") (pintype "passive"))
    )
    (net (code "75") (name "Net-(IC3D--IN)") (class "Default")
      (node (ref "IC3") (pin "13") (pinfunction "-IN_13") (pintype "input"))
      (node (ref "R26") (pin "1") (pinfunction "1_1") (pintype "passive"))
      (node (ref "R27") (pin "1") (pinfunction "1_1") (pintype "passive"))
    )
    (net (code "76") (name "Net-(IC4-Pad1)") (class "Default")
      (node (ref "IC4") (pin "1") (pinfunction "1_1") (pintype "bidirectional"))
      (node (ref "R33") (pin "2") (pinfunction "2_2") (pintype "passive"))
    )
    (net (code "77") (name "Net-(IC4A-4)") (class "Default")
      (node (ref "IC4") (pin "7") (pinfunction "4_7") (pintype "bidirectional"))
      (node (ref "R40") (pin "1") (pinfunction "1_1") (pintype "passive"))
      (node (ref "R41") (pin "1") (pinfunction "1_1") (pintype "passive"))
    )
    (net (code "78") (name "Net-(IC4B-1)") (class "Default")
      (node (ref "IC4") (pin "3") (pinfunction "1_3") (pintype "bidirectional"))
      (node (ref "R32") (pin "2") (pinfunction "2_2") (pintype "passive"))
    )
    (net (code "79") (name "Net-(IC4B-4)") (class "Default")
      (node (ref "IC4") (pin "5") (pinfunction "4_5") (pintype "bidirectional"))
      (node (ref "R38") (pin "1") (pinfunction "1_1") (pintype "passive"))
      (node (ref "R39") (pin "1") (pinfunction "1_1") (pintype "passive"))
    )
    (net (code "80") (name "Net-(LED1-C)") (class "Default")
      (node (ref "LED1") (pin "K") (pinfunction "C_K") (pintype "passive"))
      (node (ref "LED2") (pin "A") (pinfunction "A_A") (pintype "passive"))
      (node (ref "R14") (pin "1") (pinfunction "1_1") (pintype "passive"))
    )
    (net (code "81") (name "Net-(LED3-C)") (class "Default")
      (node (ref "LED3") (pin "K") (pinfunction "C_K") (pintype "passive"))
      (node (ref "LED4") (pin "A") (pinfunction "A_A") (pintype "passive"))
      (node (ref "R16") (pin "1") (pinfunction "1_1") (pintype "passive"))
    )
    (net (code "82") (name "Net-(LED5-C)") (class "Default")
      (node (ref "LED5") (pin "K") (pinfunction "C_K") (pintype "passive"))
      (node (ref "LED6") (pin "A") (pinfunction "A_A") (pintype "passive"))
      (node (ref "R21") (pin "1") (pinfunction "1_1") (pintype "passive"))
    )
    (net (code "83") (name "Net-(LED7-C)") (class "Default")
      (node (ref "LED7") (pin "K") (pinfunction "C_K") (pintype "passive"))
      (node (ref "LED8") (pin "A") (pinfunction "A_A") (pintype "passive"))
      (node (ref "R23") (pin "1") (pinfunction "1_1") (pintype "passive"))
    )
    (net (code "84") (name "Net-(R5-Pad2)") (class "Default")
      (node (ref "R5") (pin "2") (pinfunction "2_2") (pintype "passive"))
      (node (ref "T1") (pin "B") (pinfunction "B_B") (pintype "passive"))
    )
    (net (code "85") (name "Net-(R8-Pad2)") (class "Default")
      (node (ref "R8") (pin "2") (pinfunction "2_2") (pintype "passive"))
      (node (ref "T2") (pin "B") (pinfunction "B_B") (pintype "passive"))
    )
    (net (code "86") (name "Net-(R39-Pad2)") (class "Default")
      (node (ref "R39") (pin "2") (pinfunction "2_2") (pintype "passive"))
      (node (ref "T3") (pin "B") (pinfunction "B_B") (pintype "passive"))
    )
    (net (code "87") (name "Net-(R41-Pad2)") (class "Default")
      (node (ref "R41") (pin "2") (pinfunction "2_2") (pintype "passive"))
      (node (ref "T4") (pin "B") (pinfunction "B_B") (pintype "passive"))
    )
    (net (code "88") (name "Net-(U$1-ALERT)") (class "Default")
      (node (ref "R1") (pin "1") (pinfunction "1_1") (pintype "passive"))
      (node (ref "U$1") (pin "11") (pinfunction "ALERT_11") (pintype "bidirectional"))
    )
    (net (code "89") (name "Net-(U$1-RSA)") (class "Default")
      (node (ref "R15") (pin "1") (pinfunction "1_1") (pintype "passive"))
      (node (ref "R2") (pin "1") (pinfunction "1_1") (pintype "passive"))
      (node (ref "U$1") (pin "8") (pinfunction "RSA_8") (pintype "bidirectional"))
    )
    (net (code "90") (name "Net-(U$1-VCC)") (class "Default")
      (node (ref "C1") (pin "+") (pinfunction "+_+") (pintype "passive"))
      (node (ref "C3") (pin "2") (pinfunction "2_2") (pintype "passive"))
      (node (ref "F1") (pin "1") (pinfunction "1_1") (pintype "passive"))
      (node (ref "U$1") (pin "5") (pinfunction "VCC_5") (pintype "bidirectional"))
    )
    (net (code "91") (name "Net-(U$1-VREG)") (class "Default")
      (node (ref "C4") (pin "1") (pinfunction "1_1") (pintype "passive"))
      (node (ref "U$1") (pin "15") (pinfunction "VREG_15") (pintype "bidirectional"))
    )
    (net (code "92") (name "Net-(U$2-ALERT)") (class "Default")
      (node (ref "R11") (pin "1") (pinfunction "1_1") (pintype "passive"))
      (node (ref "U$2") (pin "11") (pinfunction "ALERT_11") (pintype "bidirectional"))
    )
    (net (code "93") (name "Net-(U$2-RSA)") (class "Default")
      (node (ref "R10") (pin "1") (pinfunction "1_1") (pintype "passive"))
      (node (ref "R12") (pin "1") (pinfunction "1_1") (pintype "passive"))
      (node (ref "U$2") (pin "8") (pinfunction "RSA_8") (pintype "bidirectional"))
    )
    (net (code "94") (name "Net-(U$2-VCC)") (class "Default")
      (node (ref "C2") (pin "+") (pinfunction "+_+") (pintype "passive"))
      (node (ref "C6") (pin "2") (pinfunction "2_2") (pintype "passive"))
      (node (ref "F2") (pin "1") (pinfunction "1_1") (pintype "passive"))
      (node (ref "U$2") (pin "5") (pinfunction "VCC_5") (pintype "bidirectional"))
    )
    (net (code "95") (name "Net-(U$2-VREG)") (class "Default")
      (node (ref "C7") (pin "1") (pinfunction "1_1") (pintype "passive"))
      (node (ref "U$2") (pin "15") (pinfunction "VREG_15") (pintype "bidirectional"))
    )
    (net (code "96") (name "Net-(U$3-ALERT)") (class "Default")
      (node (ref "R31") (pin "1") (pinfunction "1_1") (pintype "passive"))
      (node (ref "U$3") (pin "11") (pinfunction "ALERT_11") (pintype "bidirectional"))
    )
    (net (code "97") (name "Net-(U$3-RSA)") (class "Default")
      (node (ref "R29") (pin "1") (pinfunction "1_1") (pintype "passive"))
      (node (ref "R30") (pin "1") (pinfunction "1_1") (pintype "passive"))
      (node (ref "U$3") (pin "8") (pinfunction "RSA_8") (pintype "bidirectional"))
    )
    (net (code "98") (name "Net-(U$3-VCC)") (class "Default")
      (node (ref "C20") (pin "2") (pinfunction "2_2") (pintype "passive"))
      (node (ref "C26") (pin "+") (pinfunction "+_+") (pintype "passive"))
      (node (ref "F4") (pin "1") (pinfunction "1_1") (pintype "passive"))
      (node (ref "U$3") (pin "5") (pinfunction "VCC_5") (pintype "bidirectional"))
    )
    (net (code "99") (name "Net-(U$3-VREG)") (class "Default")
      (node (ref "C19") (pin "1") (pinfunction "1_1") (pintype "passive"))
      (node (ref "U$3") (pin "15") (pinfunction "VREG_15") (pintype "bidirectional"))
    )
    (net (code "100") (name "Net-(U$4-ALERT)") (class "Default")
      (node (ref "R37") (pin "1") (pinfunction "1_1") (pintype "passive"))
      (node (ref "U$4") (pin "11") (pinfunction "ALERT_11") (pintype "bidirectional"))
    )
    (net (code "101") (name "Net-(U$4-RSA)") (class "Default")
      (node (ref "R35") (pin "1") (pinfunction "1_1") (pintype "passive"))
      (node (ref "R36") (pin "1") (pinfunction "1_1") (pintype "passive"))
      (node (ref "U$4") (pin "8") (pinfunction "RSA_8") (pintype "bidirectional"))
    )
    (net (code "102") (name "Net-(U$4-VCC)") (class "Default")
      (node (ref "C25") (pin "2") (pinfunction "2_2") (pintype "passive"))
      (node (ref "C28") (pin "+") (pinfunction "+_+") (pintype "passive"))
      (node (ref "F5") (pin "1") (pinfunction "1_1") (pintype "passive"))
      (node (ref "U$4") (pin "5") (pinfunction "VCC_5") (pintype "bidirectional"))
    )
    (net (code "103") (name "Net-(U$4-VREG)") (class "Default")
      (node (ref "C27") (pin "1") (pinfunction "1_1") (pintype "passive"))
      (node (ref "U$4") (pin "15") (pinfunction "VREG_15") (pintype "bidirectional"))
    )
    (net (code "104") (name "SCK") (class "Default")
      (node (ref "CONN") (pin "13") (pinfunction "13_SCK_13") (pintype "bidirectional"))
      (node (ref "IC2") (pin "3") (pinfunction "(SCK/PCINT15)PB7_3") (pintype "bidirectional"))
    )
    (net (code "105") (name "TCK") (class "Default")
      (node (ref "IC2") (pin "21") (pinfunction "(TCK/PCINT18)PC2_21") (pintype "bidirectional"))
      (node (ref "JP1") (pin "1") (pinfunction "1_1") (pintype "passive"))
    )
    (net (code "106") (name "TDI") (class "Default")
      (node (ref "IC2") (pin "24") (pinfunction "(TDI/PCINT21)PC5_24") (pintype "bidirectional"))
      (node (ref "JP1") (pin "9") (pinfunction "9_9") (pintype "passive"))
    )
    (net (code "107") (name "TDO") (class "Default")
      (node (ref "IC2") (pin "23") (pinfunction "(TDO/PCINT20)PC4_23") (pintype "bidirectional"))
      (node (ref "JP1") (pin "3") (pinfunction "3_3") (pintype "passive"))
    )
    (net (code "108") (name "TMS") (class "Default")
      (node (ref "IC2") (pin "22") (pinfunction "(TMS/PCINT19)PC3_22") (pintype "bidirectional"))
      (node (ref "JP1") (pin "5") (pinfunction "5_5") (pintype "passive"))
    )
    (net (code "109") (name "unconnected-(CONN-10_3.3V-Pad10)") (class "Default")
      (node (ref "CONN") (pin "10") (pinfunction "10_3.3V_10") (pintype "bidirectional"))
    )
    (net (code "110") (name "unconnected-(JP1-Pad8)") (class "Default")
      (node (ref "JP1") (pin "8") (pinfunction "8_8") (pintype "passive"))
    )
    (net (code "111") (name "unconnected-(U$1-NC-Pad6)") (class "Default")
      (node (ref "U$1") (pin "6") (pinfunction "NC_6") (pintype "bidirectional"))
    )
    (net (code "112") (name "unconnected-(U$2-NC-Pad6)") (class "Default")
      (node (ref "U$2") (pin "6") (pinfunction "NC_6") (pintype "bidirectional"))
    )
    (net (code "113") (name "unconnected-(U$3-NC-Pad6)") (class "Default")
      (node (ref "U$3") (pin "6") (pinfunction "NC_6") (pintype "bidirectional"))
    )
    (net (code "114") (name "unconnected-(U$4-NC-Pad6)") (class "Default")
      (node (ref "U$4") (pin "6") (pinfunction "NC_6") (pintype "bidirectional"))
    )
  )
)
